# main.net
KiCad netlist of a schematic drawn in Altium Designer
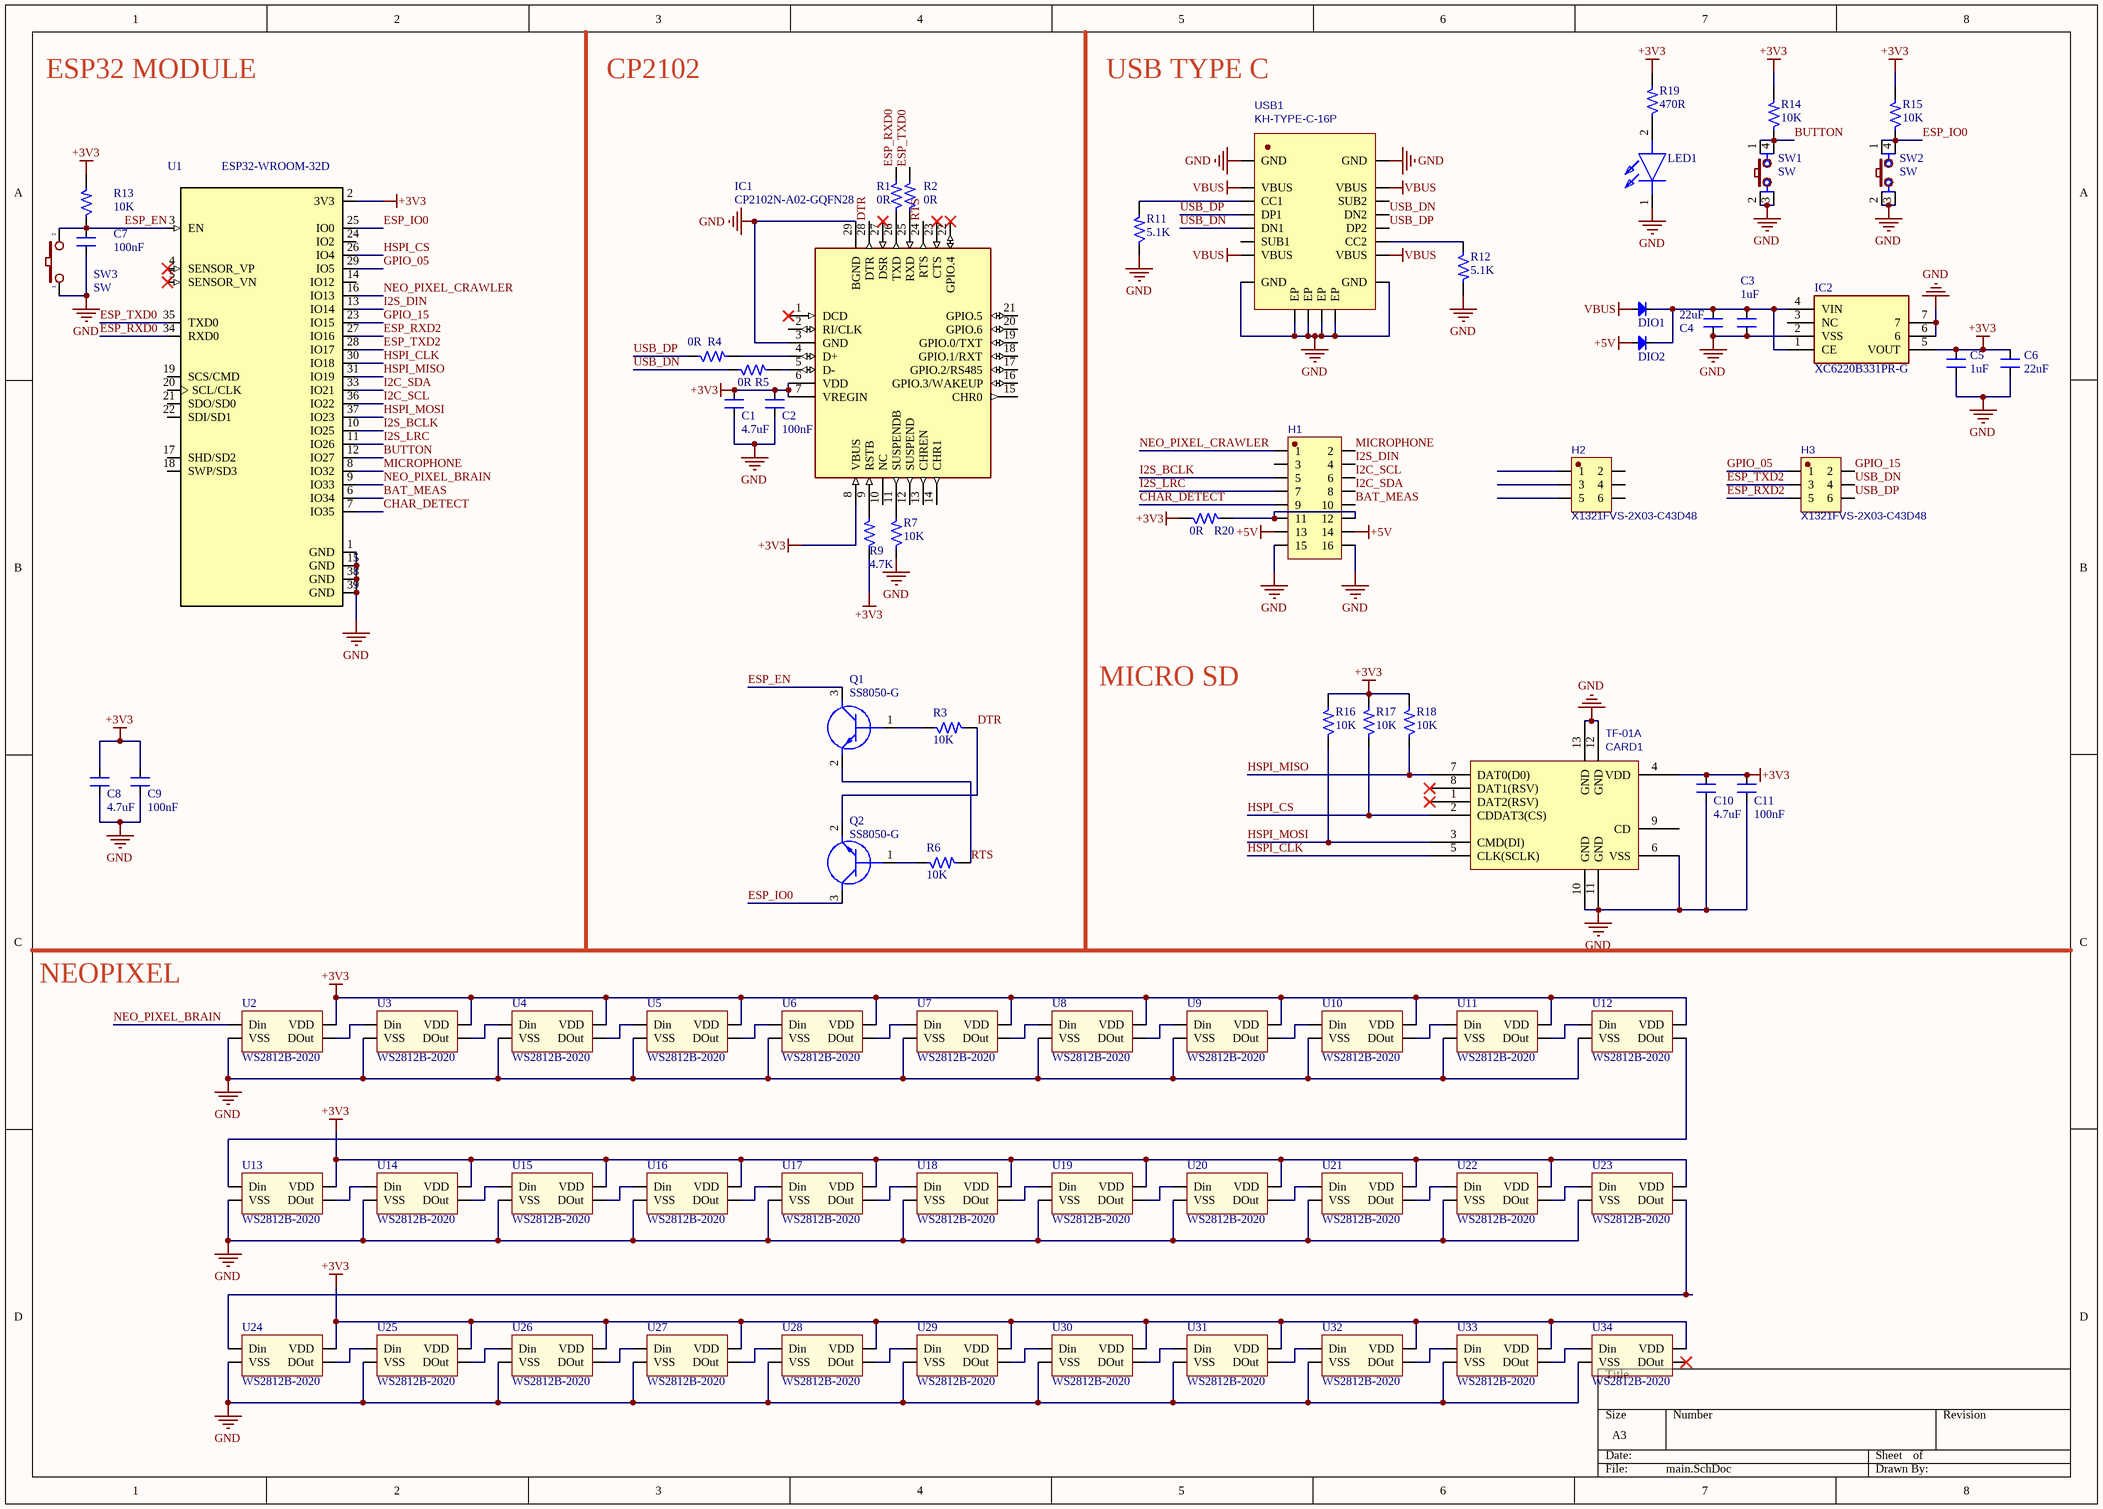
[diagram p0: main.SchDoc]

(export (version "E")
  (design (tool "Eeschema 10.0.6"))
  (components
    (comp (ref "C1")
      (value "4.7uF")
      (footprint "CAP_0402")
      (description "4.7µF ±10% 10V Ceramic Capacitor X5R 0402 (1005 Metric)")
      (fields
        (field (name "MANUFACTURER") "Samsung Electro-Mechanics")
        (field (name "MANUFACTURER PART NUMBER") "CL05A475KP5NRNC")
      )
      (libsource (lib "EsteemPCB_SOM_Course_schlib") (part "CAP_4.7uF-10V-10%-0402"))
    )
    (comp (ref "C2")
      (value "100nF")
      (footprint "CAP_0402")
      (description "0.1µF ±10% 10V Ceramic Capacitor X7R 0402 (1005 Metric)")
      (fields
        (field (name "MANUFACTURER") "Yageo")
        (field (name "MANUFACTURER PART NUMBER") "CC0402KRX7R6BB104")
      )
      (libsource (lib "EsteemPCB_SOM_Course_schlib") (part "CAP_100nF-10V-10%-0402"))
    )
    (comp (ref "C3")
      (value "1uF")
      (footprint "CAP_0402")
      (description "1µF ±10% 10V Ceramic Capacitor X6S 0402 (1005 Metric)")
      (fields
        (field (name "MANUFACTURER") "Murata Electronics")
        (field (name "MANUFACTURER PART NUMBER") "GRT155C81A105KE01D")
      )
      (libsource (lib "EsteemPCB_SOM_Course_schlib") (part "CAP_1uF-10V-10%-0402"))
    )
    (comp (ref "C4")
      (value "22uF")
      (footprint "CAP_0603")
      (description "22µF ±20% 10V Ceramic Capacitor X5R 0603 (1608 Metric)")
      (fields
        (field (name "MANUFACTURER") "Murata Electronics")
        (field (name "MANUFACTURER PART NUMBER") "GRM188R61A226ME15D")
      )
      (libsource (lib "EsteemPCB_SOM_Course_schlib") (part "CAP_22uF-10V-20%-0603"))
    )
    (comp (ref "C5")
      (value "1uF")
      (footprint "CAP_0402")
      (description "1µF ±10% 10V Ceramic Capacitor X6S 0402 (1005 Metric)")
      (fields
        (field (name "MANUFACTURER") "Murata Electronics")
        (field (name "MANUFACTURER PART NUMBER") "GRT155C81A105KE01D")
      )
      (libsource (lib "EsteemPCB_SOM_Course_schlib") (part "CAP_1uF-10V-10%-0402"))
    )
    (comp (ref "C6")
      (value "22uF")
      (footprint "CAP_0603")
      (description "22µF ±20% 10V Ceramic Capacitor X5R 0603 (1608 Metric)")
      (fields
        (field (name "MANUFACTURER") "Murata Electronics")
        (field (name "MANUFACTURER PART NUMBER") "GRM188R61A226ME15D")
      )
      (libsource (lib "EsteemPCB_SOM_Course_schlib") (part "CAP_22uF-10V-20%-0603"))
    )
    (comp (ref "C7")
      (value "100nF")
      (footprint "CAP_0402")
      (description "0.1µF ±10% 10V Ceramic Capacitor X7R 0402 (1005 Metric)")
      (fields
        (field (name "MANUFACTURER") "Yageo")
        (field (name "MANUFACTURER PART NUMBER") "CC0402KRX7R6BB104")
      )
      (libsource (lib "EsteemPCB_SOM_Course_schlib") (part "CAP_100nF-10V-10%-0402"))
    )
    (comp (ref "C8")
      (value "4.7uF")
      (footprint "CAP_0402")
      (description "4.7µF ±10% 10V Ceramic Capacitor X5R 0402 (1005 Metric)")
      (fields
        (field (name "MANUFACTURER") "Samsung Electro-Mechanics")
        (field (name "MANUFACTURER PART NUMBER") "CL05A475KP5NRNC")
      )
      (libsource (lib "EsteemPCB_SOM_Course_schlib") (part "CAP_4.7uF-10V-10%-0402"))
    )
    (comp (ref "C9")
      (value "100nF")
      (footprint "CAP_0402")
      (description "0.1µF ±10% 10V Ceramic Capacitor X7R 0402 (1005 Metric)")
      (fields
        (field (name "MANUFACTURER") "Yageo")
        (field (name "MANUFACTURER PART NUMBER") "CC0402KRX7R6BB104")
      )
      (libsource (lib "EsteemPCB_SOM_Course_schlib") (part "CAP_100nF-10V-10%-0402"))
    )
    (comp (ref "C10")
      (value "4.7uF")
      (footprint "CAP_0402")
      (description "4.7µF ±10% 10V Ceramic Capacitor X5R 0402 (1005 Metric)")
      (fields
        (field (name "MANUFACTURER") "Samsung Electro-Mechanics")
        (field (name "MANUFACTURER PART NUMBER") "CL05A475KP5NRNC")
      )
      (libsource (lib "EsteemPCB_SOM_Course_schlib") (part "CAP_4.7uF-10V-10%-0402"))
    )
    (comp (ref "C11")
      (value "100nF")
      (footprint "CAP_0402")
      (description "0.1µF ±10% 10V Ceramic Capacitor X7R 0402 (1005 Metric)")
      (fields
        (field (name "MANUFACTURER") "Yageo")
        (field (name "MANUFACTURER PART NUMBER") "CC0402KRX7R6BB104")
      )
      (libsource (lib "EsteemPCB_SOM_Course_schlib") (part "CAP_100nF-10V-10%-0402"))
    )
    (comp (ref "CARD1")
      (value "TF-01A")
      (footprint "TF-SMD_TF-01A")
      (fields (field (name "BOM_SUPPLIER PART") "C91145"))
      (libsource (lib "SamacSys") (part "TF-01A"))
    )
    (comp (ref "DIO1")
      (value "Diode SMD")
      (footprint "DIO-SMD-123")
      (description "Default Diode")
      (fields (field (name "PUBLISHER") "Altium Limited"))
      (libsource (lib "LIBRARY") (part "Diode SMD"))
    )
    (comp (ref "DIO2")
      (value "Diode SMD")
      (footprint "DIO-SMD-123")
      (description "Default Diode")
      (fields (field (name "PUBLISHER") "Altium Limited"))
      (libsource (lib "LIBRARY") (part "Diode SMD"))
    )
    (comp (ref "H1")
      (value "X1321FVS-2X08-C43D48")
      (footprint "HDR-SMD_16P-P1.27-V-F-R2-C8-LS4.8")
      (fields
        (field (name "BOM_SUPPLIER PART") "C2684736")
        (field (name "BOM_MANUFACTURER PART") "X1321FVS-2x08-C43D48")
        (field (name "CONTRIBUTOR") "LCSC")
      )
      (libsource (lib "SamacSys") (part "X1321FVS-2X08-C43D48"))
    )
    (comp (ref "H2")
      (value "X1321FVS-2X03-C43D48")
      (footprint "HDR-SMD_6P-P1.27-V-F-R2-C3-LS4.8")
      (fields
        (field (name "BOM_SUPPLIER PART") "C2684731")
        (field (name "BOM_MANUFACTURER PART") "X1321FVS-2x03-C43D48")
        (field (name "CONTRIBUTOR") "LCSC")
      )
      (libsource (lib "SamacSys") (part "X1321FVS-2X03-C43D48"))
    )
    (comp (ref "H3")
      (value "X1321FVS-2X03-C43D48")
      (footprint "HDR-SMD_6P-P1.27-V-F-R2-C3-LS4.8")
      (fields
        (field (name "BOM_SUPPLIER PART") "C2684731")
        (field (name "BOM_MANUFACTURER PART") "X1321FVS-2x03-C43D48")
        (field (name "CONTRIBUTOR") "LCSC")
      )
      (libsource (lib "SamacSys") (part "X1321FVS-2X03-C43D48"))
    )
    (comp (ref "IC1")
      (value "CP2102N-A02-GQFN28")
      (footprint "QFN50P500X500X80-29N")
      (description "Integrated Circuit")
      (fields (field (name "MOUSER2 PART NUMBER") "634-CP2102NA02GQFN28"))
      (libsource (lib "SamacSys") (part "CP2102N-A02-GQFN28"))
    )
    (comp (ref "IC2")
      (value "XC6220B331PR-G")
      (footprint "XC6220B331PRG")
      (description "Integrated Circuit")
      (fields (field (name "MOUSER PART NUMBER") "865-XC6220B331PR-G"))
      (libsource (lib "*") (part "XC6220B331PR-G"))
    )
    (comp (ref "LED1")
      (value "LTST-C190KRKT")
      (footprint "LEDC1608X80N")
      (description "LED RED")
      (fields (field (name "MOUSER PART NUMBER") "859-LTST-C190KRKT"))
      (libsource (lib "SamacSys") (part "LTST-C190KRKT"))
    )
    (comp (ref "Q1")
      (value "SS8050-G")
      (footprint "SOT95P240X115-3N")
      (description "Transistor BJT NPN")
      (fields (field (name "MOUSER2 PART NUMBER") "750-SS8050-G"))
      (libsource (lib "*") (part "SS8050-G"))
    )
    (comp (ref "Q2")
      (value "SS8050-G")
      (footprint "SOT95P240X115-3N")
      (description "Transistor BJT NPN")
      (fields (field (name "MOUSER2 PART NUMBER") "750-SS8050-G"))
      (libsource (lib "*") (part "SS8050-G"))
    )
    (comp (ref "R1")
      (value "0R")
      (footprint "RES_0402")
      (description "0 Ohms Jumper 0.1W, 1/10W Chip Resistor 0402 (1005 Metric) Automotive AEC-Q200 Thick Film")
      (fields
        (field (name "MANUFACTURER") "Panasonic Electronic Components")
        (field (name "MANUFACTURER PART NUMBER") "ERJ-2GE0R00X")
      )
      (libsource (lib "EsteemPCB_SOM_Course_schlib") (part "RES_0R-0.1W-1%-0402"))
    )
    (comp (ref "R2")
      (value "0R")
      (footprint "RES_0402")
      (description "0 Ohms Jumper 0.1W, 1/10W Chip Resistor 0402 (1005 Metric) Automotive AEC-Q200 Thick Film")
      (fields
        (field (name "MANUFACTURER") "Panasonic Electronic Components")
        (field (name "MANUFACTURER PART NUMBER") "ERJ-2GE0R00X")
      )
      (libsource (lib "EsteemPCB_SOM_Course_schlib") (part "RES_0R-0.1W-1%-0402"))
    )
    (comp (ref "R3")
      (value "10K")
      (footprint "RES_0402")
      (description "10 kOhms ±1% 0.1W, 1/10W Chip Resistor 0402 (1005 Metric) Anti-Sulfur Thin Film")
      (fields
        (field (name "MANUFACTURER") "Vishay Beyschlag/Draloric/BC Components")
        (field (name "MANUFACTURER PART NUMBER") "MCS04020C1002FE000")
      )
      (libsource (lib "EsteemPCB_SOM_Course_schlib") (part "RES_10K-0.1W-1%-0402"))
    )
    (comp (ref "R4")
      (value "0R")
      (footprint "RES_0402")
      (description "0 Ohms Jumper 0.1W, 1/10W Chip Resistor 0402 (1005 Metric) Automotive AEC-Q200 Thick Film")
      (fields
        (field (name "MANUFACTURER") "Panasonic Electronic Components")
        (field (name "MANUFACTURER PART NUMBER") "ERJ-2GE0R00X")
      )
      (libsource (lib "EsteemPCB_SOM_Course_schlib") (part "RES_0R-0.1W-1%-0402"))
    )
    (comp (ref "R5")
      (value "0R")
      (footprint "RES_0402")
      (description "0 Ohms Jumper 0.1W, 1/10W Chip Resistor 0402 (1005 Metric) Automotive AEC-Q200 Thick Film")
      (fields
        (field (name "MANUFACTURER") "Panasonic Electronic Components")
        (field (name "MANUFACTURER PART NUMBER") "ERJ-2GE0R00X")
      )
      (libsource (lib "EsteemPCB_SOM_Course_schlib") (part "RES_0R-0.1W-1%-0402"))
    )
    (comp (ref "R6")
      (value "10K")
      (footprint "RES_0402")
      (description "10 kOhms ±1% 0.1W, 1/10W Chip Resistor 0402 (1005 Metric) Anti-Sulfur Thin Film")
      (fields
        (field (name "MANUFACTURER") "Vishay Beyschlag/Draloric/BC Components")
        (field (name "MANUFACTURER PART NUMBER") "MCS04020C1002FE000")
      )
      (libsource (lib "EsteemPCB_SOM_Course_schlib") (part "RES_10K-0.1W-1%-0402"))
    )
    (comp (ref "R7")
      (value "10K")
      (footprint "RES_0402")
      (description "10 kOhms ±1% 0.1W, 1/10W Chip Resistor 0402 (1005 Metric) Anti-Sulfur Thin Film")
      (fields
        (field (name "MANUFACTURER") "Vishay Beyschlag/Draloric/BC Components")
        (field (name "MANUFACTURER PART NUMBER") "MCS04020C1002FE000")
      )
      (libsource (lib "EsteemPCB_SOM_Course_schlib") (part "RES_10K-0.1W-1%-0402"))
    )
    (comp (ref "R9")
      (value "4.7K")
      (footprint "RES_0402")
      (description "4.7 kOhms ±1% 0.1W, 1/10W Chip Resistor 0402 (1005 Metric) Automotive AEC-Q200 Thick Film")
      (fields
        (field (name "MANUFACTURER") "Panasonic Electronic Components")
        (field (name "MANUFACTURER PART NUMBER") "ERJ-2RKF4701X")
      )
      (libsource (lib "EsteemPCB_SOM_Course_schlib") (part "RES_4.7K-0.1W-1%-0402"))
    )
    (comp (ref "R11")
      (value "5.1K")
      (footprint "RES_0402")
      (fields
        (field (name "MANUFACTURER") "KOA Speer Electronics, Inc.")
        (field (name "MANUFACTURER PART NUMBER") "RK73H1ETTP5601F")
      )
      (libsource (lib "EsteemPCB_SOM_Course_schlib") (part "RES_5.6K-0.1W-1%-0402"))
    )
    (comp (ref "R12")
      (value "5.1K")
      (footprint "RES_0402")
      (fields
        (field (name "MANUFACTURER") "KOA Speer Electronics, Inc.")
        (field (name "MANUFACTURER PART NUMBER") "RK73H1ETTP5601F")
      )
      (libsource (lib "EsteemPCB_SOM_Course_schlib") (part "RES_5.6K-0.1W-1%-0402"))
    )
    (comp (ref "R13")
      (value "10K")
      (footprint "RES_0402")
      (description "10 kOhms ±1% 0.1W, 1/10W Chip Resistor 0402 (1005 Metric) Anti-Sulfur Thin Film")
      (fields
        (field (name "MANUFACTURER") "Vishay Beyschlag/Draloric/BC Components")
        (field (name "MANUFACTURER PART NUMBER") "MCS04020C1002FE000")
      )
      (libsource (lib "EsteemPCB_SOM_Course_schlib") (part "RES_10K-0.1W-1%-0402"))
    )
    (comp (ref "R14")
      (value "10K")
      (footprint "RES_0402")
      (description "10 kOhms ±1% 0.1W, 1/10W Chip Resistor 0402 (1005 Metric) Anti-Sulfur Thin Film")
      (fields
        (field (name "MANUFACTURER") "Vishay Beyschlag/Draloric/BC Components")
        (field (name "MANUFACTURER PART NUMBER") "MCS04020C1002FE000")
      )
      (libsource (lib "EsteemPCB_SOM_Course_schlib") (part "RES_10K-0.1W-1%-0402"))
    )
    (comp (ref "R15")
      (value "10K")
      (footprint "RES_0402")
      (description "10 kOhms ±1% 0.1W, 1/10W Chip Resistor 0402 (1005 Metric) Anti-Sulfur Thin Film")
      (fields
        (field (name "MANUFACTURER") "Vishay Beyschlag/Draloric/BC Components")
        (field (name "MANUFACTURER PART NUMBER") "MCS04020C1002FE000")
      )
      (libsource (lib "EsteemPCB_SOM_Course_schlib") (part "RES_10K-0.1W-1%-0402"))
    )
    (comp (ref "R16")
      (value "10K")
      (footprint "RES_0402")
      (description "10 kOhms ±1% 0.1W, 1/10W Chip Resistor 0402 (1005 Metric) Anti-Sulfur Thin Film")
      (fields
        (field (name "MANUFACTURER") "Vishay Beyschlag/Draloric/BC Components")
        (field (name "MANUFACTURER PART NUMBER") "MCS04020C1002FE000")
      )
      (libsource (lib "EsteemPCB_SOM_Course_schlib") (part "RES_10K-0.1W-1%-0402"))
    )
    (comp (ref "R17")
      (value "10K")
      (footprint "RES_0402")
      (description "10 kOhms ±1% 0.1W, 1/10W Chip Resistor 0402 (1005 Metric) Anti-Sulfur Thin Film")
      (fields
        (field (name "MANUFACTURER") "Vishay Beyschlag/Draloric/BC Components")
        (field (name "MANUFACTURER PART NUMBER") "MCS04020C1002FE000")
      )
      (libsource (lib "EsteemPCB_SOM_Course_schlib") (part "RES_10K-0.1W-1%-0402"))
    )
    (comp (ref "R18")
      (value "10K")
      (footprint "RES_0402")
      (description "10 kOhms ±1% 0.1W, 1/10W Chip Resistor 0402 (1005 Metric) Anti-Sulfur Thin Film")
      (fields
        (field (name "MANUFACTURER") "Vishay Beyschlag/Draloric/BC Components")
        (field (name "MANUFACTURER PART NUMBER") "MCS04020C1002FE000")
      )
      (libsource (lib "EsteemPCB_SOM_Course_schlib") (part "RES_10K-0.1W-1%-0402"))
    )
    (comp (ref "R19")
      (value "470R")
      (footprint "RES_0402")
      (description "470 Ohms ±1% 0.1W, 1/10W Chip Resistor 0402 (1005 Metric) Anti-Sulfur Thin Film")
      (fields
        (field (name "MANUFACTURER") "Vishay Beyschlag/Draloric/BC Components")
        (field (name "MANUFACTURER PART NUMBER") "MCS04020C1001FE000")
      )
      (libsource (lib "EsteemPCB_SOM_Course_schlib") (part "RES_1K-0.1W-1%-0402"))
    )
    (comp (ref "R20")
      (value "0R")
      (footprint "RES_0603")
      (description "0 Ohms Jumper 0.1W, 1/10W Chip Resistor 0603 (1608 Metric) Thick Film")
      (fields
        (field (name "MANUFACTURER") "Yageo")
        (field (name "MANUFACTURER PART NUMBER") "RC0603JR-070RL")
      )
      (libsource (lib "EsteemPCB_SOM_Course_schlib") (part "RES_0R-0.1W-1%-0603"))
    )
    (comp (ref "SW1")
      (value "SW")
      (footprint "SW2-DIP")
      (description "Switch button 4 pin")
      (libsource (lib "LIBRARY") (part "SW4"))
    )
    (comp (ref "SW2")
      (value "SW")
      (footprint "SW2-DIP")
      (description "Switch button 4 pin")
      (libsource (lib "LIBRARY") (part "SW4"))
    )
    (comp (ref "SW3")
      (value "SW")
      (footprint "SW1-SMD")
      (description "Switch button 2 pin")
      (libsource (lib "LIBRARY") (part "SW2"))
    )
    (comp (ref "U1")
      (value "ESP32-WROOM-32D")
      (footprint "ESP32WROOM32D16MB")
      (description "IC: SoC; GPIO, I2C, I2S, IR, SD, SDIO, SPI, UART; 2.7Ã·3.6VDC; 20dBm")
      (fields (field (name "MF") "Espressif Systems"))
      (libsource (lib "SamacSys") (part "ESP32-WROOM-32D"))
    )
    (comp (ref "U2")
      (value "WS2812B-2020")
      (footprint "WS2812-2020")
      (libsource (lib "SamacSys") (part "WS2812B"))
    )
    (comp (ref "U3")
      (value "WS2812B-2020")
      (footprint "WS2812-2020")
      (libsource (lib "SamacSys") (part "WS2812B"))
    )
    (comp (ref "U4")
      (value "WS2812B-2020")
      (footprint "WS2812-2020")
      (libsource (lib "SamacSys") (part "WS2812B"))
    )
    (comp (ref "U5")
      (value "WS2812B-2020")
      (footprint "WS2812-2020")
      (libsource (lib "SamacSys") (part "WS2812B"))
    )
    (comp (ref "U6")
      (value "WS2812B-2020")
      (footprint "WS2812-2020")
      (libsource (lib "SamacSys") (part "WS2812B"))
    )
    (comp (ref "U7")
      (value "WS2812B-2020")
      (footprint "WS2812-2020")
      (libsource (lib "SamacSys") (part "WS2812B"))
    )
    (comp (ref "U8")
      (value "WS2812B-2020")
      (footprint "WS2812-2020")
      (libsource (lib "SamacSys") (part "WS2812B"))
    )
    (comp (ref "U9")
      (value "WS2812B-2020")
      (footprint "WS2812-2020")
      (libsource (lib "SamacSys") (part "WS2812B"))
    )
    (comp (ref "U10")
      (value "WS2812B-2020")
      (footprint "WS2812-2020")
      (libsource (lib "SamacSys") (part "WS2812B"))
    )
    (comp (ref "U11")
      (value "WS2812B-2020")
      (footprint "WS2812-2020")
      (libsource (lib "SamacSys") (part "WS2812B"))
    )
    (comp (ref "U12")
      (value "WS2812B-2020")
      (footprint "WS2812-2020")
      (libsource (lib "SamacSys") (part "WS2812B"))
    )
    (comp (ref "U13")
      (value "WS2812B-2020")
      (footprint "WS2812-2020")
      (libsource (lib "SamacSys") (part "WS2812B"))
    )
    (comp (ref "U14")
      (value "WS2812B-2020")
      (footprint "WS2812-2020")
      (libsource (lib "SamacSys") (part "WS2812B"))
    )
    (comp (ref "U15")
      (value "WS2812B-2020")
      (footprint "WS2812-2020")
      (libsource (lib "SamacSys") (part "WS2812B"))
    )
    (comp (ref "U16")
      (value "WS2812B-2020")
      (footprint "WS2812-2020")
      (libsource (lib "SamacSys") (part "WS2812B"))
    )
    (comp (ref "U17")
      (value "WS2812B-2020")
      (footprint "WS2812-2020")
      (libsource (lib "SamacSys") (part "WS2812B"))
    )
    (comp (ref "U18")
      (value "WS2812B-2020")
      (footprint "WS2812-2020")
      (libsource (lib "SamacSys") (part "WS2812B"))
    )
    (comp (ref "U19")
      (value "WS2812B-2020")
      (footprint "WS2812-2020")
      (libsource (lib "SamacSys") (part "WS2812B"))
    )
    (comp (ref "U20")
      (value "WS2812B-2020")
      (footprint "WS2812-2020")
      (libsource (lib "SamacSys") (part "WS2812B"))
    )
    (comp (ref "U21")
      (value "WS2812B-2020")
      (footprint "WS2812-2020")
      (libsource (lib "SamacSys") (part "WS2812B"))
    )
    (comp (ref "U22")
      (value "WS2812B-2020")
      (footprint "WS2812-2020")
      (libsource (lib "SamacSys") (part "WS2812B"))
    )
    (comp (ref "U23")
      (value "WS2812B-2020")
      (footprint "WS2812-2020")
      (libsource (lib "SamacSys") (part "WS2812B"))
    )
    (comp (ref "U24")
      (value "WS2812B-2020")
      (footprint "WS2812-2020")
      (libsource (lib "SamacSys") (part "WS2812B"))
    )
    (comp (ref "U25")
      (value "WS2812B-2020")
      (footprint "WS2812-2020")
      (libsource (lib "SamacSys") (part "WS2812B"))
    )
    (comp (ref "U26")
      (value "WS2812B-2020")
      (footprint "WS2812-2020")
      (libsource (lib "SamacSys") (part "WS2812B"))
    )
    (comp (ref "U27")
      (value "WS2812B-2020")
      (footprint "WS2812-2020")
      (libsource (lib "SamacSys") (part "WS2812B"))
    )
    (comp (ref "U28")
      (value "WS2812B-2020")
      (footprint "WS2812-2020")
      (libsource (lib "SamacSys") (part "WS2812B"))
    )
    (comp (ref "U29")
      (value "WS2812B-2020")
      (footprint "WS2812-2020")
      (libsource (lib "SamacSys") (part "WS2812B"))
    )
    (comp (ref "U30")
      (value "WS2812B-2020")
      (footprint "WS2812-2020")
      (libsource (lib "SamacSys") (part "WS2812B"))
    )
    (comp (ref "U31")
      (value "WS2812B-2020")
      (footprint "WS2812-2020")
      (libsource (lib "SamacSys") (part "WS2812B"))
    )
    (comp (ref "U32")
      (value "WS2812B-2020")
      (footprint "WS2812-2020")
      (libsource (lib "SamacSys") (part "WS2812B"))
    )
    (comp (ref "U33")
      (value "WS2812B-2020")
      (footprint "WS2812-2020")
      (libsource (lib "SamacSys") (part "WS2812B"))
    )
    (comp (ref "U34")
      (value "WS2812B-2020")
      (footprint "WS2812-2020")
      (libsource (lib "SamacSys") (part "WS2812B"))
    )
    (comp (ref "USB1")
      (value "KH-TYPE-C-16P")
      (footprint "USB-C-SMD_KH-TYPE-C-16P")
      (fields (field (name "BOM_SUPPLIER PART") "C709357") (field (name "CONTRIBUTOR") "LCSC"))
      (libsource (lib "SamacSys") (part "KH-TYPE-C-16P"))
    )
  )
  (nets
    (net (code "1") (name "+3V3") (class "Default")
      (node (ref "C1") (pin "2") (pinfunction "2_2") (pintype "passive"))
      (node (ref "C10") (pin "2") (pinfunction "2_2") (pintype "passive"))
      (node (ref "C11") (pin "2") (pinfunction "2_2") (pintype "passive"))
      (node (ref "C2") (pin "2") (pinfunction "2_2") (pintype "passive"))
      (node (ref "C5") (pin "2") (pinfunction "2_2") (pintype "passive"))
      (node (ref "C6") (pin "2") (pinfunction "2_2") (pintype "passive"))
      (node (ref "C8") (pin "2") (pinfunction "2_2") (pintype "passive"))
      (node (ref "C9") (pin "2") (pinfunction "2_2") (pintype "passive"))
      (node (ref "CARD1") (pin "4") (pinfunction "VDD_4") (pintype "passive"))
      (node (ref "IC1") (pin "6") (pinfunction "VDD_6") (pintype "power_in"))
      (node (ref "IC1") (pin "7") (pinfunction "VREGIN_7") (pintype "power_in"))
      (node (ref "IC1") (pin "8") (pinfunction "VBUS_8") (pintype "input"))
      (node (ref "IC2") (pin "5") (pinfunction "VOUT_5") (pintype "passive"))
      (node (ref "R13") (pin "2") (pinfunction "2_2") (pintype "passive"))
      (node (ref "R14") (pin "2") (pinfunction "2_2") (pintype "passive"))
      (node (ref "R15") (pin "2") (pinfunction "2_2") (pintype "passive"))
      (node (ref "R16") (pin "2") (pinfunction "2_2") (pintype "passive"))
      (node (ref "R17") (pin "2") (pinfunction "2_2") (pintype "passive"))
      (node (ref "R18") (pin "2") (pinfunction "2_2") (pintype "passive"))
      (node (ref "R19") (pin "2") (pinfunction "2_2") (pintype "passive"))
      (node (ref "R20") (pin "1") (pinfunction "1_1") (pintype "passive"))
      (node (ref "R9") (pin "1") (pinfunction "1_1") (pintype "passive"))
      (node (ref "U1") (pin "2") (pinfunction "3V3_2") (pintype "power_in"))
      (node (ref "U10") (pin "1") (pinfunction "VDD_1") (pintype "passive"))
      (node (ref "U11") (pin "1") (pinfunction "VDD_1") (pintype "passive"))
      (node (ref "U12") (pin "1") (pinfunction "VDD_1") (pintype "passive"))
      (node (ref "U13") (pin "1") (pinfunction "VDD_1") (pintype "passive"))
      (node (ref "U14") (pin "1") (pinfunction "VDD_1") (pintype "passive"))
      (node (ref "U15") (pin "1") (pinfunction "VDD_1") (pintype "passive"))
      (node (ref "U16") (pin "1") (pinfunction "VDD_1") (pintype "passive"))
      (node (ref "U17") (pin "1") (pinfunction "VDD_1") (pintype "passive"))
      (node (ref "U18") (pin "1") (pinfunction "VDD_1") (pintype "passive"))
      (node (ref "U19") (pin "1") (pinfunction "VDD_1") (pintype "passive"))
      (node (ref "U2") (pin "1") (pinfunction "VDD_1") (pintype "passive"))
      (node (ref "U20") (pin "1") (pinfunction "VDD_1") (pintype "passive"))
      (node (ref "U21") (pin "1") (pinfunction "VDD_1") (pintype "passive"))
      (node (ref "U22") (pin "1") (pinfunction "VDD_1") (pintype "passive"))
      (node (ref "U23") (pin "1") (pinfunction "VDD_1") (pintype "passive"))
      (node (ref "U24") (pin "1") (pinfunction "VDD_1") (pintype "passive"))
      (node (ref "U25") (pin "1") (pinfunction "VDD_1") (pintype "passive"))
      (node (ref "U26") (pin "1") (pinfunction "VDD_1") (pintype "passive"))
      (node (ref "U27") (pin "1") (pinfunction "VDD_1") (pintype "passive"))
      (node (ref "U28") (pin "1") (pinfunction "VDD_1") (pintype "passive"))
      (node (ref "U29") (pin "1") (pinfunction "VDD_1") (pintype "passive"))
      (node (ref "U3") (pin "1") (pinfunction "VDD_1") (pintype "passive"))
      (node (ref "U30") (pin "1") (pinfunction "VDD_1") (pintype "passive"))
      (node (ref "U31") (pin "1") (pinfunction "VDD_1") (pintype "passive"))
      (node (ref "U32") (pin "1") (pinfunction "VDD_1") (pintype "passive"))
      (node (ref "U33") (pin "1") (pinfunction "VDD_1") (pintype "passive"))
      (node (ref "U34") (pin "1") (pinfunction "VDD_1") (pintype "passive"))
      (node (ref "U4") (pin "1") (pinfunction "VDD_1") (pintype "passive"))
      (node (ref "U5") (pin "1") (pinfunction "VDD_1") (pintype "passive"))
      (node (ref "U6") (pin "1") (pinfunction "VDD_1") (pintype "passive"))
      (node (ref "U7") (pin "1") (pinfunction "VDD_1") (pintype "passive"))
      (node (ref "U8") (pin "1") (pinfunction "VDD_1") (pintype "passive"))
      (node (ref "U9") (pin "1") (pinfunction "VDD_1") (pintype "passive"))
    )
    (net (code "2") (name "+5V") (class "Default")
      (node (ref "DIO2") (pin "1") (pinfunction "A_1") (pintype "passive"))
      (node (ref "H1") (pin "13") (pinfunction "13_13") (pintype "passive"))
      (node (ref "H1") (pin "14") (pinfunction "14_14") (pintype "passive"))
    )
    (net (code "3") (name "/BAT_MEAS") (class "Default")
      (node (ref "H1") (pin "10") (pinfunction "10_10") (pintype "passive"))
      (node (ref "U1") (pin "6") (pinfunction "IO34_6") (pintype "bidirectional"))
    )
    (net (code "4") (name "/BUTTON") (class "Default")
      (node (ref "R14") (pin "1") (pinfunction "1_1") (pintype "passive"))
      (node (ref "SW1") (pin "1") (pintype "passive"))
      (node (ref "SW1") (pin "4") (pinfunction "4_4") (pintype "passive"))
      (node (ref "U1") (pin "12") (pinfunction "IO27_12") (pintype "bidirectional"))
    )
    (net (code "5") (name "/CHAR_DETECT") (class "Default")
      (node (ref "H1") (pin "9") (pinfunction "9_9") (pintype "passive"))
      (node (ref "U1") (pin "7") (pinfunction "IO35_7") (pintype "bidirectional"))
    )
    (net (code "6") (name "/DTR") (class "Default")
      (node (ref "IC1") (pin "28") (pinfunction "DTR_28") (pintype "output"))
      (node (ref "Q2") (pin "2") (pinfunction "E_2") (pintype "passive"))
      (node (ref "R3") (pin "2") (pinfunction "2_2") (pintype "passive"))
    )
    (net (code "7") (name "/ESP_EN") (class "Default")
      (node (ref "C7") (pin "2") (pinfunction "2_2") (pintype "passive"))
      (node (ref "Q1") (pin "3") (pinfunction "C_3") (pintype "passive"))
      (node (ref "R13") (pin "1") (pinfunction "1_1") (pintype "passive"))
      (node (ref "SW3") (pin "2") (pinfunction "2_2") (pintype "passive"))
      (node (ref "U1") (pin "3") (pinfunction "EN_3") (pintype "input"))
    )
    (net (code "8") (name "/ESP_IO0") (class "Default")
      (node (ref "Q2") (pin "3") (pinfunction "C_3") (pintype "passive"))
      (node (ref "R15") (pin "1") (pinfunction "1_1") (pintype "passive"))
      (node (ref "SW2") (pin "1") (pintype "passive"))
      (node (ref "SW2") (pin "4") (pinfunction "4_4") (pintype "passive"))
      (node (ref "U1") (pin "25") (pinfunction "IO0_25") (pintype "bidirectional"))
    )
    (net (code "9") (name "/ESP_RXD0") (class "Default")
      (node (ref "R1") (pin "2") (pinfunction "2_2") (pintype "passive"))
      (node (ref "U1") (pin "34") (pinfunction "RXD0_34") (pintype "bidirectional"))
    )
    (net (code "10") (name "/ESP_RXD2") (class "Default")
      (node (ref "H3") (pin "5") (pinfunction "5_5") (pintype "passive"))
      (node (ref "U1") (pin "27") (pinfunction "IO16_27") (pintype "bidirectional"))
    )
    (net (code "11") (name "/ESP_TXD0") (class "Default")
      (node (ref "R2") (pin "2") (pinfunction "2_2") (pintype "passive"))
      (node (ref "U1") (pin "35") (pinfunction "TXD0_35") (pintype "bidirectional"))
    )
    (net (code "12") (name "/ESP_TXD2") (class "Default")
      (node (ref "H3") (pin "3") (pinfunction "3_3") (pintype "passive"))
      (node (ref "U1") (pin "28") (pinfunction "IO17_28") (pintype "bidirectional"))
    )
    (net (code "13") (name "/GPIO_05") (class "Default")
      (node (ref "H3") (pin "1") (pinfunction "1_1") (pintype "passive"))
      (node (ref "U1") (pin "29") (pinfunction "IO5_29") (pintype "bidirectional"))
    )
    (net (code "14") (name "/GPIO_15") (class "Default")
      (node (ref "H3") (pin "2") (pinfunction "2_2") (pintype "passive"))
      (node (ref "U1") (pin "23") (pinfunction "IO15_23") (pintype "bidirectional"))
    )
    (net (code "15") (name "/HSPI_CLK") (class "Default")
      (node (ref "CARD1") (pin "5") (pinfunction "CLK(SCLK)_5") (pintype "passive"))
      (node (ref "U1") (pin "30") (pinfunction "IO18_30") (pintype "bidirectional"))
    )
    (net (code "16") (name "/HSPI_CS") (class "Default")
      (node (ref "CARD1") (pin "2") (pinfunction "CDDAT3(CS)_2") (pintype "passive"))
      (node (ref "R17") (pin "1") (pinfunction "1_1") (pintype "passive"))
      (node (ref "U1") (pin "26") (pinfunction "IO4_26") (pintype "bidirectional"))
    )
    (net (code "17") (name "/HSPI_MISO") (class "Default")
      (node (ref "CARD1") (pin "7") (pinfunction "DAT0(D0)_7") (pintype "passive"))
      (node (ref "R18") (pin "1") (pinfunction "1_1") (pintype "passive"))
      (node (ref "U1") (pin "31") (pinfunction "IO19_31") (pintype "bidirectional"))
    )
    (net (code "18") (name "/HSPI_MOSI") (class "Default")
      (node (ref "CARD1") (pin "3") (pinfunction "CMD(DI)_3") (pintype "passive"))
      (node (ref "R16") (pin "1") (pinfunction "1_1") (pintype "passive"))
      (node (ref "U1") (pin "37") (pinfunction "IO23_37") (pintype "bidirectional"))
    )
    (net (code "19") (name "/I2C_SCL") (class "Default")
      (node (ref "H1") (pin "6") (pinfunction "6_6") (pintype "passive"))
      (node (ref "U1") (pin "36") (pinfunction "IO22_36") (pintype "bidirectional"))
    )
    (net (code "20") (name "/I2C_SDA") (class "Default")
      (node (ref "H1") (pin "8") (pinfunction "8_8") (pintype "passive"))
      (node (ref "U1") (pin "33") (pinfunction "IO21_33") (pintype "bidirectional"))
    )
    (net (code "21") (name "/I2S_BCLK") (class "Default")
      (node (ref "H1") (pin "5") (pinfunction "5_5") (pintype "passive"))
      (node (ref "U1") (pin "10") (pinfunction "IO25_10") (pintype "bidirectional"))
    )
    (net (code "22") (name "/I2S_DIN") (class "Default")
      (node (ref "H1") (pin "4") (pinfunction "4_4") (pintype "passive"))
      (node (ref "U1") (pin "13") (pinfunction "IO14_13") (pintype "bidirectional"))
    )
    (net (code "23") (name "/I2S_LRC") (class "Default")
      (node (ref "H1") (pin "7") (pinfunction "7_7") (pintype "passive"))
      (node (ref "U1") (pin "11") (pinfunction "IO26_11") (pintype "bidirectional"))
    )
    (net (code "24") (name "/MICROPHONE") (class "Default")
      (node (ref "H1") (pin "2") (pinfunction "2_2") (pintype "passive"))
      (node (ref "U1") (pin "8") (pinfunction "IO32_8") (pintype "bidirectional"))
    )
    (net (code "25") (name "/NEO_PIXEL_BRAIN") (class "Default")
      (node (ref "U1") (pin "9") (pinfunction "IO33_9") (pintype "bidirectional"))
      (node (ref "U2") (pin "4") (pinfunction "Din_4") (pintype "passive"))
    )
    (net (code "26") (name "/NEO_PIXEL_CRAWLER") (class "Default")
      (node (ref "H1") (pin "1") (pinfunction "1_1") (pintype "passive"))
      (node (ref "U1") (pin "16") (pinfunction "IO13_16") (pintype "bidirectional"))
    )
    (net (code "27") (name "/RTS") (class "Default")
      (node (ref "IC1") (pin "24") (pinfunction "RTS_24") (pintype "output"))
      (node (ref "Q1") (pin "2") (pinfunction "E_2") (pintype "passive"))
      (node (ref "R6") (pin "2") (pinfunction "2_2") (pintype "passive"))
    )
    (net (code "28") (name "/USB_DN") (class "Default")
      (node (ref "H3") (pin "4") (pinfunction "4_4") (pintype "passive"))
      (node (ref "R5") (pin "1") (pinfunction "1_1") (pintype "passive"))
      (node (ref "USB1") (pin "A7") (pinfunction "DN1_A7") (pintype "passive"))
      (node (ref "USB1") (pin "B7") (pinfunction "DN2_B7") (pintype "passive"))
    )
    (net (code "29") (name "/USB_DP") (class "Default")
      (node (ref "H3") (pin "6") (pinfunction "6_6") (pintype "passive"))
      (node (ref "R4") (pin "1") (pinfunction "1_1") (pintype "passive"))
      (node (ref "USB1") (pin "A6") (pinfunction "DP1_A6") (pintype "passive"))
      (node (ref "USB1") (pin "B6") (pinfunction "DP2_B6") (pintype "passive"))
    )
    (net (code "30") (name "GND") (class "Default")
      (node (ref "C1") (pin "1") (pinfunction "1_1") (pintype "passive"))
      (node (ref "C10") (pin "1") (pinfunction "1_1") (pintype "passive"))
      (node (ref "C11") (pin "1") (pinfunction "1_1") (pintype "passive"))
      (node (ref "C2") (pin "1") (pinfunction "1_1") (pintype "passive"))
      (node (ref "C3") (pin "1") (pinfunction "1_1") (pintype "passive"))
      (node (ref "C4") (pin "1") (pinfunction "1_1") (pintype "passive"))
      (node (ref "C5") (pin "1") (pinfunction "1_1") (pintype "passive"))
      (node (ref "C6") (pin "1") (pinfunction "1_1") (pintype "passive"))
      (node (ref "C7") (pin "1") (pinfunction "1_1") (pintype "passive"))
      (node (ref "C8") (pin "1") (pinfunction "1_1") (pintype "passive"))
      (node (ref "C9") (pin "1") (pinfunction "1_1") (pintype "passive"))
      (node (ref "CARD1") (pin "10") (pinfunction "GND_10") (pintype "passive"))
      (node (ref "CARD1") (pin "11") (pinfunction "GND_11") (pintype "passive"))
      (node (ref "CARD1") (pin "12") (pinfunction "GND_12") (pintype "passive"))
      (node (ref "CARD1") (pin "13") (pinfunction "GND_13") (pintype "passive"))
      (node (ref "CARD1") (pin "6") (pinfunction "VSS_6") (pintype "passive"))
      (node (ref "H1") (pin "15") (pinfunction "15_15") (pintype "passive"))
      (node (ref "H1") (pin "16") (pinfunction "16_16") (pintype "passive"))
      (node (ref "IC1") (pin "29") (pinfunction "BGND_29") (pintype "power_in"))
      (node (ref "IC1") (pin "3") (pinfunction "GND_3") (pintype "power_in"))
      (node (ref "IC2") (pin "2") (pinfunction "VSS_2") (pintype "passive"))
      (node (ref "IC2") (pin "6") (pinfunction "6_6") (pintype "passive"))
      (node (ref "IC2") (pin "7") (pinfunction "7_7") (pintype "passive"))
      (node (ref "LED1") (pin "1") (pinfunction "K_1") (pintype "passive"))
      (node (ref "R11") (pin "1") (pinfunction "1_1") (pintype "passive"))
      (node (ref "R12") (pin "2") (pinfunction "2_2") (pintype "passive"))
      (node (ref "R7") (pin "1") (pinfunction "1_1") (pintype "passive"))
      (node (ref "SW1") (pin "2") (pinfunction "2_2") (pintype "passive"))
      (node (ref "SW1") (pin "3") (pinfunction "3_3") (pintype "passive"))
      (node (ref "SW2") (pin "2") (pinfunction "2_2") (pintype "passive"))
      (node (ref "SW2") (pin "3") (pinfunction "3_3") (pintype "passive"))
      (node (ref "SW3") (pin "1") (pinfunction "1_1") (pintype "passive"))
      (node (ref "U1") (pin "1") (pinfunction "GND_1") (pintype "power_in"))
      (node (ref "U1") (pin "15") (pinfunction "GND_15") (pintype "power_in"))
      (node (ref "U1") (pin "38") (pinfunction "GND_38") (pintype "power_in"))
      (node (ref "U1") (pin "39") (pinfunction "GND_39") (pintype "power_in"))
      (node (ref "U10") (pin "3") (pinfunction "VSS_3") (pintype "passive"))
      (node (ref "U11") (pin "3") (pinfunction "VSS_3") (pintype "passive"))
      (node (ref "U12") (pin "3") (pinfunction "VSS_3") (pintype "passive"))
      (node (ref "U13") (pin "3") (pinfunction "VSS_3") (pintype "passive"))
      (node (ref "U14") (pin "3") (pinfunction "VSS_3") (pintype "passive"))
      (node (ref "U15") (pin "3") (pinfunction "VSS_3") (pintype "passive"))
      (node (ref "U16") (pin "3") (pinfunction "VSS_3") (pintype "passive"))
      (node (ref "U17") (pin "3") (pinfunction "VSS_3") (pintype "passive"))
      (node (ref "U18") (pin "3") (pinfunction "VSS_3") (pintype "passive"))
      (node (ref "U19") (pin "3") (pinfunction "VSS_3") (pintype "passive"))
      (node (ref "U2") (pin "3") (pinfunction "VSS_3") (pintype "passive"))
      (node (ref "U20") (pin "3") (pinfunction "VSS_3") (pintype "passive"))
      (node (ref "U21") (pin "3") (pinfunction "VSS_3") (pintype "passive"))
      (node (ref "U22") (pin "3") (pinfunction "VSS_3") (pintype "passive"))
      (node (ref "U23") (pin "3") (pinfunction "VSS_3") (pintype "passive"))
      (node (ref "U24") (pin "3") (pinfunction "VSS_3") (pintype "passive"))
      (node (ref "U25") (pin "3") (pinfunction "VSS_3") (pintype "passive"))
      (node (ref "U26") (pin "3") (pinfunction "VSS_3") (pintype "passive"))
      (node (ref "U27") (pin "3") (pinfunction "VSS_3") (pintype "passive"))
      (node (ref "U28") (pin "3") (pinfunction "VSS_3") (pintype "passive"))
      (node (ref "U29") (pin "3") (pinfunction "VSS_3") (pintype "passive"))
      (node (ref "U3") (pin "3") (pinfunction "VSS_3") (pintype "passive"))
      (node (ref "U30") (pin "3") (pinfunction "VSS_3") (pintype "passive"))
      (node (ref "U31") (pin "3") (pinfunction "VSS_3") (pintype "passive"))
      (node (ref "U32") (pin "3") (pinfunction "VSS_3") (pintype "passive"))
      (node (ref "U33") (pin "3") (pinfunction "VSS_3") (pintype "passive"))
      (node (ref "U34") (pin "3") (pinfunction "VSS_3") (pintype "passive"))
      (node (ref "U4") (pin "3") (pinfunction "VSS_3") (pintype "passive"))
      (node (ref "U5") (pin "3") (pinfunction "VSS_3") (pintype "passive"))
      (node (ref "U6") (pin "3") (pinfunction "VSS_3") (pintype "passive"))
      (node (ref "U7") (pin "3") (pinfunction "VSS_3") (pintype "passive"))
      (node (ref "U8") (pin "3") (pinfunction "VSS_3") (pintype "passive"))
      (node (ref "U9") (pin "3") (pinfunction "VSS_3") (pintype "passive"))
      (node (ref "USB1") (pin "1") (pinfunction "EP_1") (pintype "passive"))
      (node (ref "USB1") (pin "2") (pinfunction "EP_2") (pintype "passive"))
      (node (ref "USB1") (pin "3") (pinfunction "EP_3") (pintype "passive"))
      (node (ref "USB1") (pin "4") (pinfunction "EP_4") (pintype "passive"))
      (node (ref "USB1") (pin "A1") (pinfunction "GND_A1") (pintype "passive"))
      (node (ref "USB1") (pin "A12") (pinfunction "GND_A12") (pintype "passive"))
      (node (ref "USB1") (pin "B1") (pinfunction "GND_B1") (pintype "passive"))
      (node (ref "USB1") (pin "B12") (pinfunction "GND_B12") (pintype "passive"))
    )
    (net (code "31") (name "Net-(DIO1-K)") (class "Default")
      (node (ref "C3") (pin "2") (pinfunction "2_2") (pintype "passive"))
      (node (ref "C4") (pin "2") (pinfunction "2_2") (pintype "passive"))
      (node (ref "DIO1") (pin "2") (pinfunction "K_2") (pintype "passive"))
      (node (ref "DIO2") (pin "2") (pinfunction "K_2") (pintype "passive"))
      (node (ref "IC2") (pin "1") (pinfunction "CE_1") (pintype "passive"))
      (node (ref "IC2") (pin "4") (pinfunction "VIN_4") (pintype "passive"))
    )
    (net (code "32") (name "Net-(H1-Pad11)") (class "Default")
      (node (ref "H1") (pin "11") (pinfunction "11_11") (pintype "passive"))
      (node (ref "H1") (pin "12") (pinfunction "12_12") (pintype "passive"))
      (node (ref "R20") (pin "2") (pinfunction "2_2") (pintype "passive"))
    )
    (net (code "33") (name "Net-(IC1-D+)") (class "Default")
      (node (ref "IC1") (pin "4") (pinfunction "D+_4") (pintype "bidirectional"))
      (node (ref "R4") (pin "2") (pinfunction "2_2") (pintype "passive"))
    )
    (net (code "34") (name "Net-(IC1-D-)") (class "Default")
      (node (ref "IC1") (pin "5") (pinfunction "D-_5") (pintype "bidirectional"))
      (node (ref "R5") (pin "2") (pinfunction "2_2") (pintype "passive"))
    )
    (net (code "35") (name "Net-(IC1-RSTB)") (class "Default")
      (node (ref "IC1") (pin "9") (pinfunction "RSTB_9") (pintype "input"))
      (node (ref "R9") (pin "2") (pinfunction "2_2") (pintype "passive"))
    )
    (net (code "36") (name "Net-(IC1-RXD)") (class "Default")
      (node (ref "IC1") (pin "25") (pinfunction "RXD_25") (pintype "input"))
      (node (ref "R2") (pin "1") (pinfunction "1_1") (pintype "passive"))
    )
    (net (code "37") (name "Net-(IC1-SUSPENDB)") (class "Default")
      (node (ref "IC1") (pin "11") (pinfunction "SUSPENDB_11") (pintype "output"))
      (node (ref "R7") (pin "2") (pinfunction "2_2") (pintype "passive"))
    )
    (net (code "38") (name "Net-(IC1-TXD)") (class "Default")
      (node (ref "IC1") (pin "26") (pinfunction "TXD_26") (pintype "output"))
      (node (ref "R1") (pin "1") (pinfunction "1_1") (pintype "passive"))
    )
    (net (code "39") (name "Net-(LED1-A)") (class "Default")
      (node (ref "LED1") (pin "2") (pinfunction "A_2") (pintype "passive"))
      (node (ref "R19") (pin "1") (pinfunction "1_1") (pintype "passive"))
    )
    (net (code "40") (name "Net-(Q1-B)") (class "Default")
      (node (ref "Q1") (pin "1") (pinfunction "B_1") (pintype "passive"))
      (node (ref "R3") (pin "1") (pinfunction "1_1") (pintype "passive"))
    )
    (net (code "41") (name "Net-(Q2-B)") (class "Default")
      (node (ref "Q2") (pin "1") (pinfunction "B_1") (pintype "passive"))
      (node (ref "R6") (pin "1") (pinfunction "1_1") (pintype "passive"))
    )
    (net (code "42") (name "Net-(U2-DOut)") (class "Default")
      (node (ref "U2") (pin "2") (pinfunction "DOut_2") (pintype "passive"))
      (node (ref "U3") (pin "4") (pinfunction "Din_4") (pintype "passive"))
    )
    (net (code "43") (name "Net-(U3-DOut)") (class "Default")
      (node (ref "U3") (pin "2") (pinfunction "DOut_2") (pintype "passive"))
      (node (ref "U4") (pin "4") (pinfunction "Din_4") (pintype "passive"))
    )
    (net (code "44") (name "Net-(U4-DOut)") (class "Default")
      (node (ref "U4") (pin "2") (pinfunction "DOut_2") (pintype "passive"))
      (node (ref "U5") (pin "4") (pinfunction "Din_4") (pintype "passive"))
    )
    (net (code "45") (name "Net-(U5-DOut)") (class "Default")
      (node (ref "U5") (pin "2") (pinfunction "DOut_2") (pintype "passive"))
      (node (ref "U6") (pin "4") (pinfunction "Din_4") (pintype "passive"))
    )
    (net (code "46") (name "Net-(U6-DOut)") (class "Default")
      (node (ref "U6") (pin "2") (pinfunction "DOut_2") (pintype "passive"))
      (node (ref "U7") (pin "4") (pinfunction "Din_4") (pintype "passive"))
    )
    (net (code "47") (name "Net-(U7-DOut)") (class "Default")
      (node (ref "U7") (pin "2") (pinfunction "DOut_2") (pintype "passive"))
      (node (ref "U8") (pin "4") (pinfunction "Din_4") (pintype "passive"))
    )
    (net (code "48") (name "Net-(U8-DOut)") (class "Default")
      (node (ref "U8") (pin "2") (pinfunction "DOut_2") (pintype "passive"))
      (node (ref "U9") (pin "4") (pinfunction "Din_4") (pintype "passive"))
    )
    (net (code "49") (name "Net-(U10-DOut)") (class "Default")
      (node (ref "U10") (pin "2") (pinfunction "DOut_2") (pintype "passive"))
      (node (ref "U11") (pin "4") (pinfunction "Din_4") (pintype "passive"))
    )
    (net (code "50") (name "Net-(U10-Din)") (class "Default")
      (node (ref "U10") (pin "4") (pinfunction "Din_4") (pintype "passive"))
      (node (ref "U9") (pin "2") (pinfunction "DOut_2") (pintype "passive"))
    )
    (net (code "51") (name "Net-(U11-DOut)") (class "Default")
      (node (ref "U11") (pin "2") (pinfunction "DOut_2") (pintype "passive"))
      (node (ref "U12") (pin "4") (pinfunction "Din_4") (pintype "passive"))
    )
    (net (code "52") (name "Net-(U12-DOut)") (class "Default")
      (node (ref "U12") (pin "2") (pinfunction "DOut_2") (pintype "passive"))
      (node (ref "U13") (pin "4") (pinfunction "Din_4") (pintype "passive"))
    )
    (net (code "53") (name "Net-(U13-DOut)") (class "Default")
      (node (ref "U13") (pin "2") (pinfunction "DOut_2") (pintype "passive"))
      (node (ref "U14") (pin "4") (pinfunction "Din_4") (pintype "passive"))
    )
    (net (code "54") (name "Net-(U14-DOut)") (class "Default")
      (node (ref "U14") (pin "2") (pinfunction "DOut_2") (pintype "passive"))
      (node (ref "U15") (pin "4") (pinfunction "Din_4") (pintype "passive"))
    )
    (net (code "55") (name "Net-(U15-DOut)") (class "Default")
      (node (ref "U15") (pin "2") (pinfunction "DOut_2") (pintype "passive"))
      (node (ref "U16") (pin "4") (pinfunction "Din_4") (pintype "passive"))
    )
    (net (code "56") (name "Net-(U16-DOut)") (class "Default")
      (node (ref "U16") (pin "2") (pinfunction "DOut_2") (pintype "passive"))
      (node (ref "U17") (pin "4") (pinfunction "Din_4") (pintype "passive"))
    )
    (net (code "57") (name "Net-(U17-DOut)") (class "Default")
      (node (ref "U17") (pin "2") (pinfunction "DOut_2") (pintype "passive"))
      (node (ref "U18") (pin "4") (pinfunction "Din_4") (pintype "passive"))
    )
    (net (code "58") (name "Net-(U18-DOut)") (class "Default")
      (node (ref "U18") (pin "2") (pinfunction "DOut_2") (pintype "passive"))
      (node (ref "U19") (pin "4") (pinfunction "Din_4") (pintype "passive"))
    )
    (net (code "59") (name "Net-(U19-DOut)") (class "Default")
      (node (ref "U19") (pin "2") (pinfunction "DOut_2") (pintype "passive"))
      (node (ref "U20") (pin "4") (pinfunction "Din_4") (pintype "passive"))
    )
    (net (code "60") (name "Net-(U20-DOut)") (class "Default")
      (node (ref "U20") (pin "2") (pinfunction "DOut_2") (pintype "passive"))
      (node (ref "U21") (pin "4") (pinfunction "Din_4") (pintype "passive"))
    )
    (net (code "61") (name "Net-(U21-DOut)") (class "Default")
      (node (ref "U21") (pin "2") (pinfunction "DOut_2") (pintype "passive"))
      (node (ref "U22") (pin "4") (pinfunction "Din_4") (pintype "passive"))
    )
    (net (code "62") (name "Net-(U22-DOut)") (class "Default")
      (node (ref "U22") (pin "2") (pinfunction "DOut_2") (pintype "passive"))
      (node (ref "U23") (pin "4") (pinfunction "Din_4") (pintype "passive"))
    )
    (net (code "63") (name "Net-(U23-DOut)") (class "Default")
      (node (ref "U23") (pin "2") (pinfunction "DOut_2") (pintype "passive"))
      (node (ref "U24") (pin "4") (pinfunction "Din_4") (pintype "passive"))
    )
    (net (code "64") (name "Net-(U24-DOut)") (class "Default")
      (node (ref "U24") (pin "2") (pinfunction "DOut_2") (pintype "passive"))
      (node (ref "U25") (pin "4") (pinfunction "Din_4") (pintype "passive"))
    )
    (net (code "65") (name "Net-(U25-DOut)") (class "Default")
      (node (ref "U25") (pin "2") (pinfunction "DOut_2") (pintype "passive"))
      (node (ref "U26") (pin "4") (pinfunction "Din_4") (pintype "passive"))
    )
    (net (code "66") (name "Net-(U26-DOut)") (class "Default")
      (node (ref "U26") (pin "2") (pinfunction "DOut_2") (pintype "passive"))
      (node (ref "U27") (pin "4") (pinfunction "Din_4") (pintype "passive"))
    )
    (net (code "67") (name "Net-(U27-DOut)") (class "Default")
      (node (ref "U27") (pin "2") (pinfunction "DOut_2") (pintype "passive"))
      (node (ref "U28") (pin "4") (pinfunction "Din_4") (pintype "passive"))
    )
    (net (code "68") (name "Net-(U28-DOut)") (class "Default")
      (node (ref "U28") (pin "2") (pinfunction "DOut_2") (pintype "passive"))
      (node (ref "U29") (pin "4") (pinfunction "Din_4") (pintype "passive"))
    )
    (net (code "69") (name "Net-(U29-DOut)") (class "Default")
      (node (ref "U29") (pin "2") (pinfunction "DOut_2") (pintype "passive"))
      (node (ref "U30") (pin "4") (pinfunction "Din_4") (pintype "passive"))
    )
    (net (code "70") (name "Net-(U30-DOut)") (class "Default")
      (node (ref "U30") (pin "2") (pinfunction "DOut_2") (pintype "passive"))
      (node (ref "U31") (pin "4") (pinfunction "Din_4") (pintype "passive"))
    )
    (net (code "71") (name "Net-(U31-DOut)") (class "Default")
      (node (ref "U31") (pin "2") (pinfunction "DOut_2") (pintype "passive"))
      (node (ref "U32") (pin "4") (pinfunction "Din_4") (pintype "passive"))
    )
    (net (code "72") (name "Net-(U32-DOut)") (class "Default")
      (node (ref "U32") (pin "2") (pinfunction "DOut_2") (pintype "passive"))
      (node (ref "U33") (pin "4") (pinfunction "Din_4") (pintype "passive"))
    )
    (net (code "73") (name "Net-(U33-DOut)") (class "Default")
      (node (ref "U33") (pin "2") (pinfunction "DOut_2") (pintype "passive"))
      (node (ref "U34") (pin "4") (pinfunction "Din_4") (pintype "passive"))
    )
    (net (code "74") (name "Net-(USB1-CC1)") (class "Default")
      (node (ref "R11") (pin "2") (pinfunction "2_2") (pintype "passive"))
      (node (ref "USB1") (pin "A5") (pinfunction "CC1_A5") (pintype "passive"))
    )
    (net (code "75") (name "Net-(USB1-CC2)") (class "Default")
      (node (ref "R12") (pin "1") (pinfunction "1_1") (pintype "passive"))
      (node (ref "USB1") (pin "B5") (pinfunction "CC2_B5") (pintype "passive"))
    )
    (net (code "76") (name "VBUS") (class "Default")
      (node (ref "DIO1") (pin "1") (pinfunction "A_1") (pintype "passive"))
      (node (ref "USB1") (pin "A4") (pinfunction "VBUS_A4") (pintype "passive"))
      (node (ref "USB1") (pin "A9") (pinfunction "VBUS_A9") (pintype "passive"))
      (node (ref "USB1") (pin "B4") (pinfunction "VBUS_B4") (pintype "passive"))
      (node (ref "USB1") (pin "B9") (pinfunction "VBUS_B9") (pintype "passive"))
    )
    (net (code "77") (name "unconnected-(CARD1-CD-Pad9)") (class "Default")
      (node (ref "CARD1") (pin "9") (pinfunction "CD_9") (pintype "passive"))
    )
    (net (code "78") (name "unconnected-(CARD1-DAT1(RSV)-Pad8)") (class "Default")
      (node (ref "CARD1") (pin "8") (pinfunction "DAT1(RSV)_8") (pintype "passive+no_connect"))
    )
    (net (code "79") (name "unconnected-(CARD1-DAT2(RSV)-Pad1)") (class "Default")
      (node (ref "CARD1") (pin "1") (pinfunction "DAT2(RSV)_1") (pintype "passive+no_connect"))
    )
    (net (code "80") (name "unconnected-(H1-Pad3)") (class "Default")
      (node (ref "H1") (pin "3") (pinfunction "3_3") (pintype "passive"))
    )
    (net (code "81") (name "unconnected-(H2-Pad1)") (class "Default")
      (node (ref "H2") (pin "1") (pinfunction "1_1") (pintype "passive"))
    )
    (net (code "82") (name "unconnected-(H2-Pad2)") (class "Default")
      (node (ref "H2") (pin "2") (pinfunction "2_2") (pintype "passive"))
    )
    (net (code "83") (name "unconnected-(H2-Pad3)") (class "Default")
      (node (ref "H2") (pin "3") (pinfunction "3_3") (pintype "passive"))
    )
    (net (code "84") (name "unconnected-(H2-Pad4)") (class "Default")
      (node (ref "H2") (pin "4") (pinfunction "4_4") (pintype "passive"))
    )
    (net (code "85") (name "unconnected-(H2-Pad5)") (class "Default")
      (node (ref "H2") (pin "5") (pinfunction "5_5") (pintype "passive"))
    )
    (net (code "86") (name "unconnected-(H2-Pad6)") (class "Default")
      (node (ref "H2") (pin "6") (pinfunction "6_6") (pintype "passive"))
    )
    (net (code "87") (name "unconnected-(IC1-CHR0-Pad15)") (class "Default")
      (node (ref "IC1") (pin "15") (pinfunction "CHR0_15") (pintype "output"))
    )
    (net (code "88") (name "unconnected-(IC1-CHR1-Pad14)") (class "Default")
      (node (ref "IC1") (pin "14") (pinfunction "CHR1_14") (pintype "output"))
    )
    (net (code "89") (name "unconnected-(IC1-CHREN-Pad13)") (class "Default")
      (node (ref "IC1") (pin "13") (pinfunction "CHREN_13") (pintype "output"))
    )
    (net (code "90") (name "unconnected-(IC1-CTS-Pad23)") (class "Default")
      (node (ref "IC1") (pin "23") (pinfunction "CTS_23") (pintype "input+no_connect"))
    )
    (net (code "91") (name "unconnected-(IC1-DCD-Pad1)") (class "Default")
      (node (ref "IC1") (pin "1") (pinfunction "DCD_1") (pintype "input+no_connect"))
    )
    (net (code "92") (name "unconnected-(IC1-DSR-Pad27)") (class "Default")
      (node (ref "IC1") (pin "27") (pinfunction "DSR_27") (pintype "input+no_connect"))
    )
    (net (code "93") (name "unconnected-(IC1-GPIO.0{slash}TXT-Pad19)") (class "Default")
      (node (ref "IC1") (pin "19") (pinfunction "GPIO.0/TXT_19") (pintype "bidirectional"))
    )
    (net (code "94") (name "unconnected-(IC1-GPIO.1{slash}RXT-Pad18)") (class "Default")
      (node (ref "IC1") (pin "18") (pinfunction "GPIO.1/RXT_18") (pintype "bidirectional"))
    )
    (net (code "95") (name "unconnected-(IC1-GPIO.2{slash}RS485-Pad17)") (class "Default")
      (node (ref "IC1") (pin "17") (pinfunction "GPIO.2/RS485_17") (pintype "bidirectional"))
    )
    (net (code "96") (name "unconnected-(IC1-GPIO.3{slash}WAKEUP-Pad16)") (class "Default")
      (node (ref "IC1") (pin "16") (pinfunction "GPIO.3/WAKEUP_16") (pintype "bidirectional"))
    )
    (net (code "97") (name "unconnected-(IC1-GPIO.4-Pad22)") (class "Default")
      (node (ref "IC1") (pin "22") (pinfunction "GPIO.4_22") (pintype "bidirectional+no_connect"))
    )
    (net (code "98") (name "unconnected-(IC1-GPIO.5-Pad21)") (class "Default")
      (node (ref "IC1") (pin "21") (pinfunction "GPIO.5_21") (pintype "bidirectional"))
    )
    (net (code "99") (name "unconnected-(IC1-GPIO.6-Pad20)") (class "Default")
      (node (ref "IC1") (pin "20") (pinfunction "GPIO.6_20") (pintype "bidirectional"))
    )
    (net (code "100") (name "unconnected-(IC1-NC-Pad10)") (class "Default")
      (node (ref "IC1") (pin "10") (pinfunction "NC_10") (pintype "passive"))
    )
    (net (code "101") (name "unconnected-(IC1-RI{slash}CLK-Pad2)") (class "Default")
      (node (ref "IC1") (pin "2") (pinfunction "RI/CLK_2") (pintype "bidirectional"))
    )
    (net (code "102") (name "unconnected-(IC1-SUSPEND-Pad12)") (class "Default")
      (node (ref "IC1") (pin "12") (pinfunction "SUSPEND_12") (pintype "output"))
    )
    (net (code "103") (name "unconnected-(IC2-NC-Pad3)") (class "Default")
      (node (ref "IC2") (pin "3") (pinfunction "NC_3") (pintype "passive"))
    )
    (net (code "104") (name "unconnected-(U1-IO2-Pad24)") (class "Default")
      (node (ref "U1") (pin "24") (pinfunction "IO2_24") (pintype "bidirectional"))
    )
    (net (code "105") (name "unconnected-(U1-IO12-Pad14)") (class "Default")
      (node (ref "U1") (pin "14") (pinfunction "IO12_14") (pintype "bidirectional"))
    )
    (net (code "106") (name "unconnected-(U1-SCL{slash}CLK-Pad20)") (class "Default")
      (node (ref "U1") (pin "20") (pinfunction "SCL/CLK_20") (pintype "bidirectional"))
    )
    (net (code "107") (name "unconnected-(U1-SCS{slash}CMD-Pad19)") (class "Default")
      (node (ref "U1") (pin "19") (pinfunction "SCS/CMD_19") (pintype "bidirectional"))
    )
    (net (code "108") (name "unconnected-(U1-SDI{slash}SD1-Pad22)") (class "Default")
      (node (ref "U1") (pin "22") (pinfunction "SDI/SD1_22") (pintype "bidirectional"))
    )
    (net (code "109") (name "unconnected-(U1-SDO{slash}SD0-Pad21)") (class "Default")
      (node (ref "U1") (pin "21") (pinfunction "SDO/SD0_21") (pintype "bidirectional"))
    )
    (net (code "110") (name "unconnected-(U1-SENSOR_VN-Pad5)") (class "Default")
      (node (ref "U1") (pin "5") (pinfunction "SENSOR_VN_5") (pintype "input+no_connect"))
    )
    (net (code "111") (name "unconnected-(U1-SENSOR_VP-Pad4)") (class "Default")
      (node (ref "U1") (pin "4") (pinfunction "SENSOR_VP_4") (pintype "input+no_connect"))
    )
    (net (code "112") (name "unconnected-(U1-SHD{slash}SD2-Pad17)") (class "Default")
      (node (ref "U1") (pin "17") (pinfunction "SHD/SD2_17") (pintype "bidirectional"))
    )
    (net (code "113") (name "unconnected-(U1-SWP{slash}SD3-Pad18)") (class "Default")
      (node (ref "U1") (pin "18") (pinfunction "SWP/SD3_18") (pintype "bidirectional"))
    )
    (net (code "114") (name "unconnected-(U34-DOut-Pad2)") (class "Default")
      (node (ref "U34") (pin "2") (pinfunction "DOut_2") (pintype "passive+no_connect"))
    )
    (net (code "115") (name "unconnected-(USB1-SUB1-PadA8)") (class "Default")
      (node (ref "USB1") (pin "A8") (pinfunction "SUB1_A8") (pintype "passive"))
    )
    (net (code "116") (name "unconnected-(USB1-SUB2-PadB8)") (class "Default")
      (node (ref "USB1") (pin "B8") (pinfunction "SUB2_B8") (pintype "passive"))
    )
  )
)
